# 6502-debugProbe.net
KiCad netlist of a schematic drawn in EasyEDA
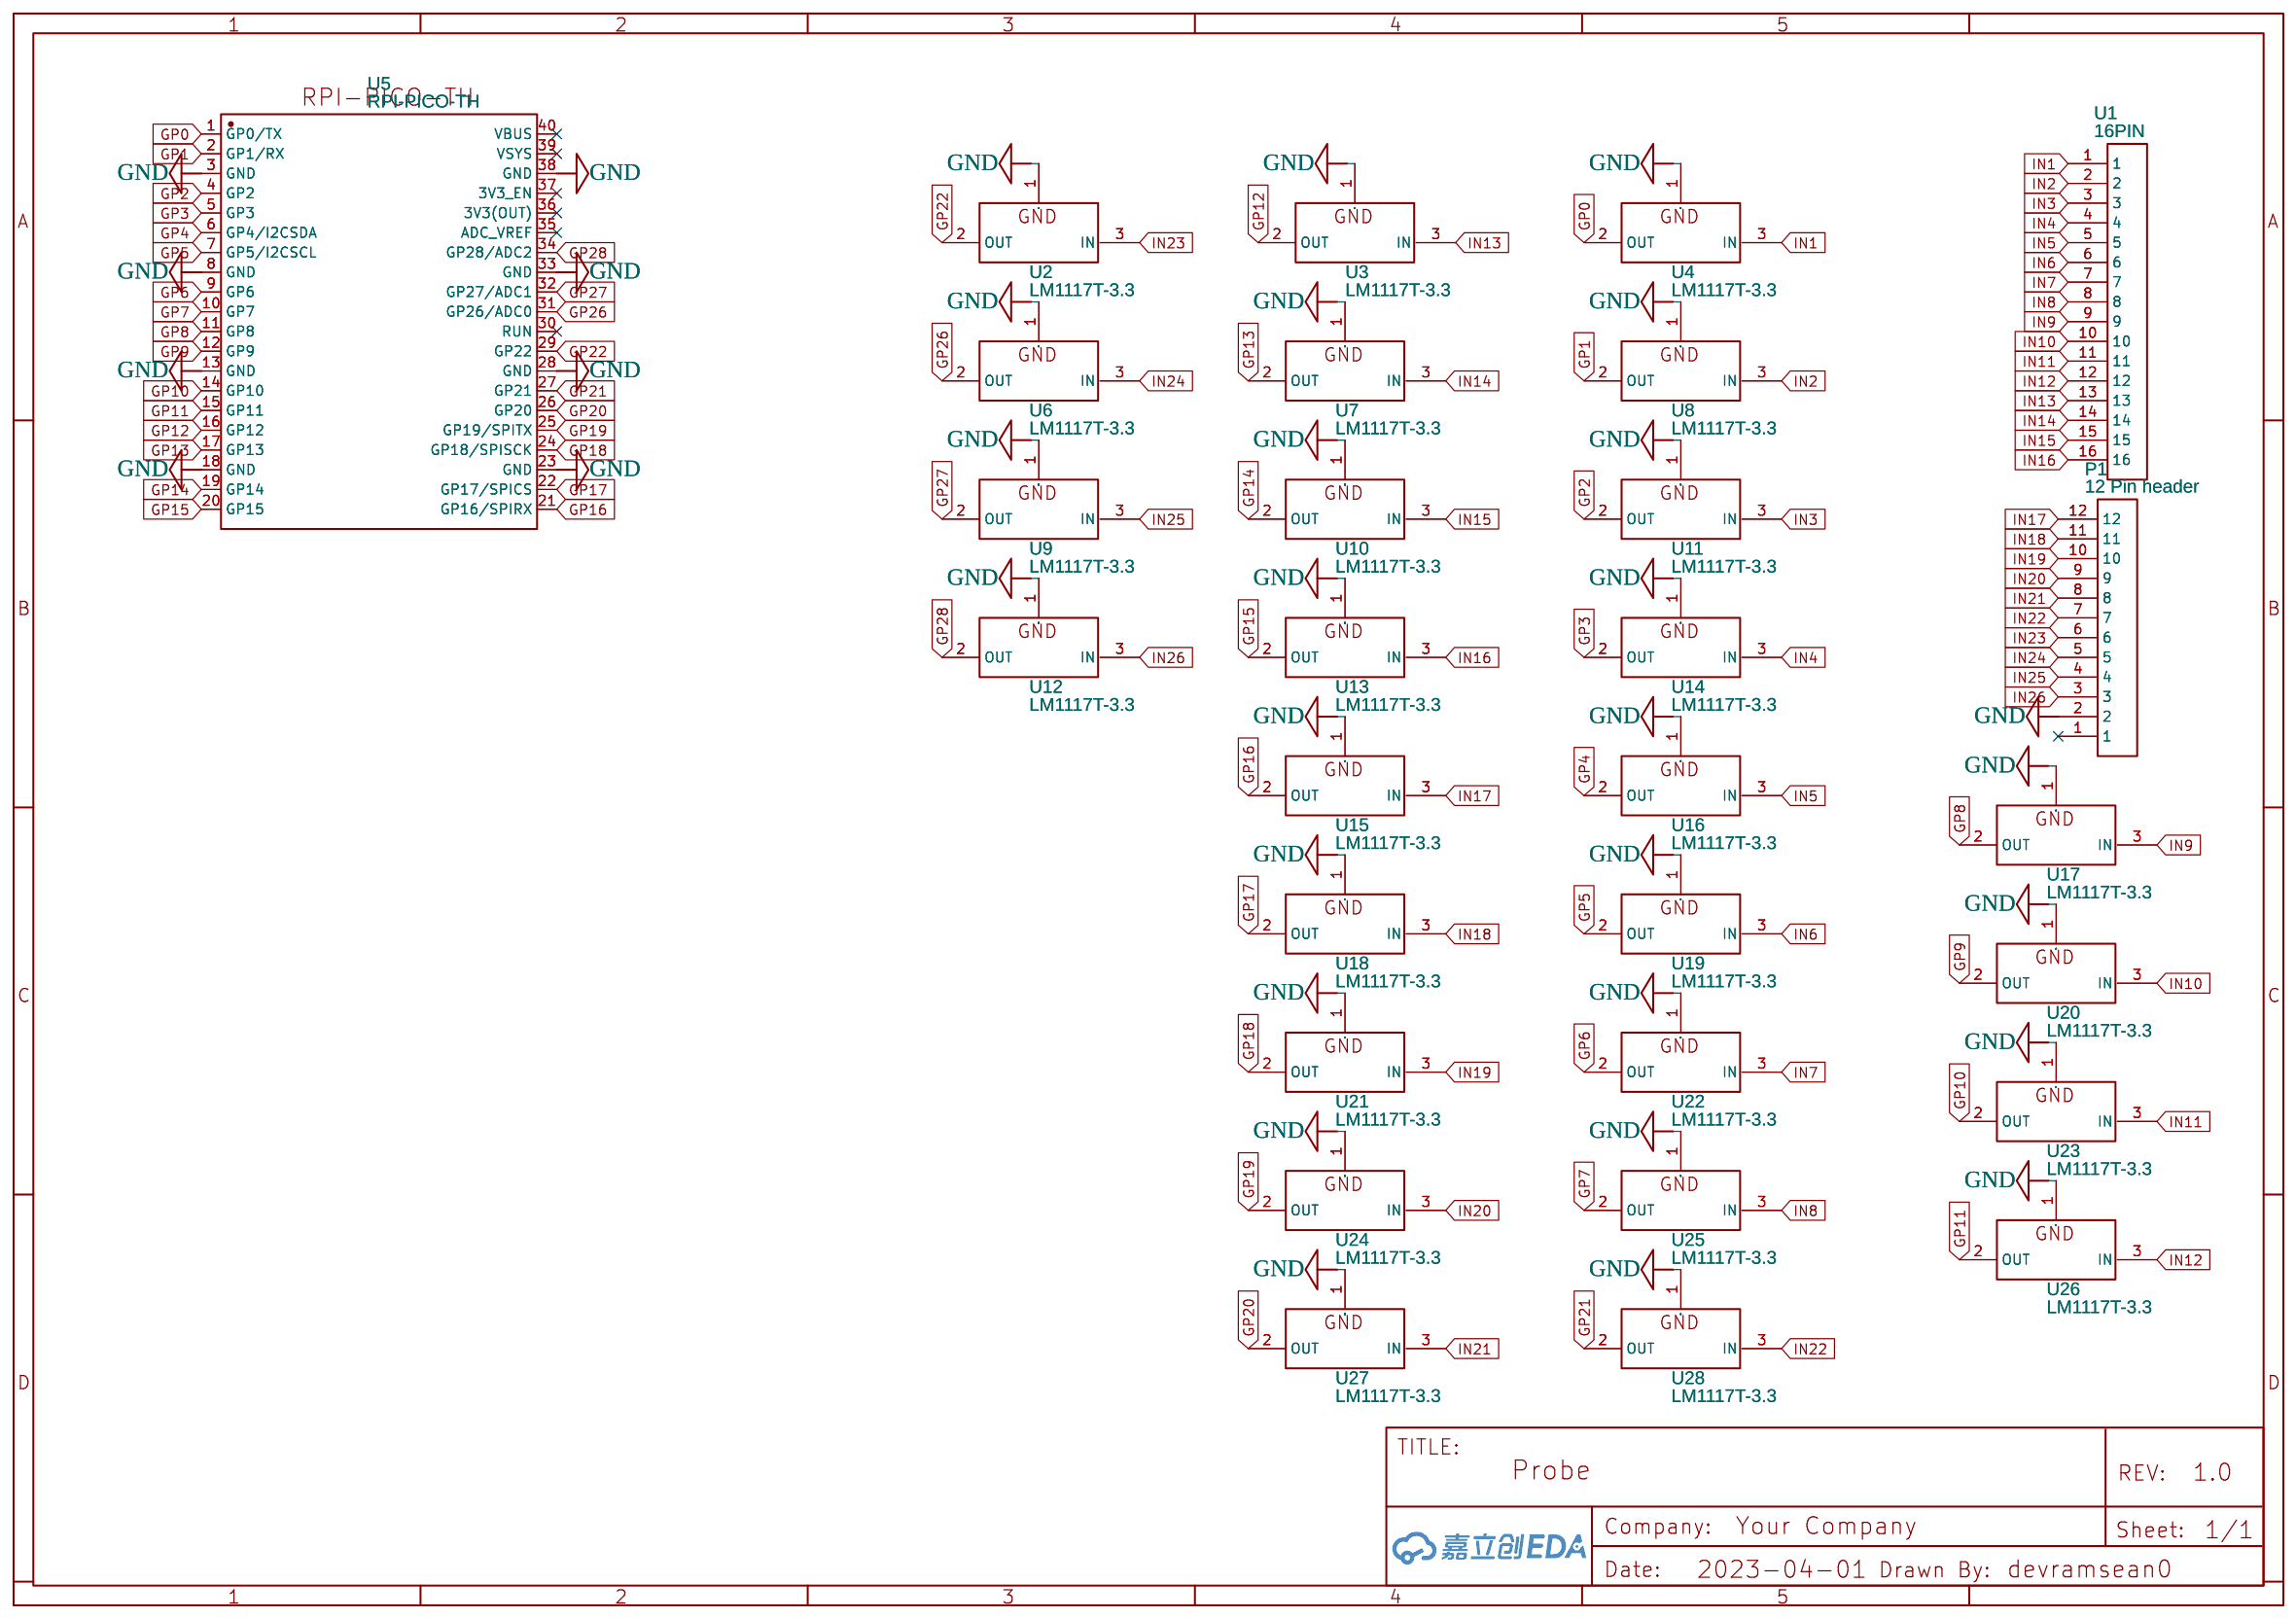
[diagram p0: schematic sheet]

(export (version "E")
  (design (tool "Eeschema 10.0.6"))
  (components
    (comp (ref "P1") (value "12 Pin header") (libsource (lib "") (part "12 Pin header")))
    (comp (ref "U1") (value "16PIN") (libsource (lib "") (part "16PIN")))
    (comp (ref "U2")
      (value "LM1117T-3.3")
      (fields (field (name "BOM_Supplier Part") "C498321"))
      (libsource (lib "") (part "LM1117T-3.3"))
    )
    (comp (ref "U3")
      (value "LM1117T-3.3")
      (fields (field (name "BOM_Supplier Part") "C498321"))
      (libsource (lib "") (part "LM1117T-3.3"))
    )
    (comp (ref "U4")
      (value "LM1117T-3.3")
      (fields (field (name "BOM_Supplier Part") "C498321"))
      (libsource (lib "") (part "LM1117T-3.3"))
    )
    (comp (ref "U5")
      (value "RPI-PICO-TH")
      (fields (field (name "BOM_Manufacturer Part") "RP2040"))
      (libsource (lib "") (part "RPI-PICO-TH"))
    )
    (comp (ref "U6")
      (value "LM1117T-3.3")
      (fields (field (name "BOM_Supplier Part") "C498321"))
      (libsource (lib "") (part "LM1117T-3.3"))
    )
    (comp (ref "U7")
      (value "LM1117T-3.3")
      (fields (field (name "BOM_Supplier Part") "C498321"))
      (libsource (lib "") (part "LM1117T-3.3"))
    )
    (comp (ref "U8")
      (value "LM1117T-3.3")
      (fields (field (name "BOM_Supplier Part") "C498321"))
      (libsource (lib "") (part "LM1117T-3.3"))
    )
    (comp (ref "U9")
      (value "LM1117T-3.3")
      (fields (field (name "BOM_Supplier Part") "C498321"))
      (libsource (lib "") (part "LM1117T-3.3"))
    )
    (comp (ref "U10")
      (value "LM1117T-3.3")
      (fields (field (name "BOM_Supplier Part") "C498321"))
      (libsource (lib "") (part "LM1117T-3.3"))
    )
    (comp (ref "U11")
      (value "LM1117T-3.3")
      (fields (field (name "BOM_Supplier Part") "C498321"))
      (libsource (lib "") (part "LM1117T-3.3"))
    )
    (comp (ref "U12")
      (value "LM1117T-3.3")
      (fields (field (name "BOM_Supplier Part") "C498321"))
      (libsource (lib "") (part "LM1117T-3.3"))
    )
    (comp (ref "U13")
      (value "LM1117T-3.3")
      (fields (field (name "BOM_Supplier Part") "C498321"))
      (libsource (lib "") (part "LM1117T-3.3"))
    )
    (comp (ref "U14")
      (value "LM1117T-3.3")
      (fields (field (name "BOM_Supplier Part") "C498321"))
      (libsource (lib "") (part "LM1117T-3.3"))
    )
    (comp (ref "U15")
      (value "LM1117T-3.3")
      (fields (field (name "BOM_Supplier Part") "C498321"))
      (libsource (lib "") (part "LM1117T-3.3"))
    )
    (comp (ref "U16")
      (value "LM1117T-3.3")
      (fields (field (name "BOM_Supplier Part") "C498321"))
      (libsource (lib "") (part "LM1117T-3.3"))
    )
    (comp (ref "U17")
      (value "LM1117T-3.3")
      (fields (field (name "BOM_Supplier Part") "C498321"))
      (libsource (lib "") (part "LM1117T-3.3"))
    )
    (comp (ref "U18")
      (value "LM1117T-3.3")
      (fields (field (name "BOM_Supplier Part") "C498321"))
      (libsource (lib "") (part "LM1117T-3.3"))
    )
    (comp (ref "U19")
      (value "LM1117T-3.3")
      (fields (field (name "BOM_Supplier Part") "C498321"))
      (libsource (lib "") (part "LM1117T-3.3"))
    )
    (comp (ref "U20")
      (value "LM1117T-3.3")
      (fields (field (name "BOM_Supplier Part") "C498321"))
      (libsource (lib "") (part "LM1117T-3.3"))
    )
    (comp (ref "U21")
      (value "LM1117T-3.3")
      (fields (field (name "BOM_Supplier Part") "C498321"))
      (libsource (lib "") (part "LM1117T-3.3"))
    )
    (comp (ref "U22")
      (value "LM1117T-3.3")
      (fields (field (name "BOM_Supplier Part") "C498321"))
      (libsource (lib "") (part "LM1117T-3.3"))
    )
    (comp (ref "U23")
      (value "LM1117T-3.3")
      (fields (field (name "BOM_Supplier Part") "C498321"))
      (libsource (lib "") (part "LM1117T-3.3"))
    )
    (comp (ref "U24")
      (value "LM1117T-3.3")
      (fields (field (name "BOM_Supplier Part") "C498321"))
      (libsource (lib "") (part "LM1117T-3.3"))
    )
    (comp (ref "U25")
      (value "LM1117T-3.3")
      (fields (field (name "BOM_Supplier Part") "C498321"))
      (libsource (lib "") (part "LM1117T-3.3"))
    )
    (comp (ref "U26")
      (value "LM1117T-3.3")
      (fields (field (name "BOM_Supplier Part") "C498321"))
      (libsource (lib "") (part "LM1117T-3.3"))
    )
    (comp (ref "U27")
      (value "LM1117T-3.3")
      (fields (field (name "BOM_Supplier Part") "C498321"))
      (libsource (lib "") (part "LM1117T-3.3"))
    )
    (comp (ref "U28")
      (value "LM1117T-3.3")
      (fields (field (name "BOM_Supplier Part") "C498321"))
      (libsource (lib "") (part "LM1117T-3.3"))
    )
  )
  (nets
    (net (code "1") (name "GND") (class "Default")
      (node (ref "P1") (pin "2") (pinfunction "2_2") (pintype "unspecified"))
      (node (ref "U10") (pin "1") (pinfunction "GND_1") (pintype "unspecified"))
      (node (ref "U11") (pin "1") (pinfunction "GND_1") (pintype "unspecified"))
      (node (ref "U12") (pin "1") (pinfunction "GND_1") (pintype "unspecified"))
      (node (ref "U13") (pin "1") (pinfunction "GND_1") (pintype "unspecified"))
      (node (ref "U14") (pin "1") (pinfunction "GND_1") (pintype "unspecified"))
      (node (ref "U15") (pin "1") (pinfunction "GND_1") (pintype "unspecified"))
      (node (ref "U16") (pin "1") (pinfunction "GND_1") (pintype "unspecified"))
      (node (ref "U17") (pin "1") (pinfunction "GND_1") (pintype "unspecified"))
      (node (ref "U18") (pin "1") (pinfunction "GND_1") (pintype "unspecified"))
      (node (ref "U19") (pin "1") (pinfunction "GND_1") (pintype "unspecified"))
      (node (ref "U2") (pin "1") (pinfunction "GND_1") (pintype "unspecified"))
      (node (ref "U20") (pin "1") (pinfunction "GND_1") (pintype "unspecified"))
      (node (ref "U21") (pin "1") (pinfunction "GND_1") (pintype "unspecified"))
      (node (ref "U22") (pin "1") (pinfunction "GND_1") (pintype "unspecified"))
      (node (ref "U23") (pin "1") (pinfunction "GND_1") (pintype "unspecified"))
      (node (ref "U24") (pin "1") (pinfunction "GND_1") (pintype "unspecified"))
      (node (ref "U25") (pin "1") (pinfunction "GND_1") (pintype "unspecified"))
      (node (ref "U26") (pin "1") (pinfunction "GND_1") (pintype "unspecified"))
      (node (ref "U27") (pin "1") (pinfunction "GND_1") (pintype "unspecified"))
      (node (ref "U28") (pin "1") (pinfunction "GND_1") (pintype "unspecified"))
      (node (ref "U3") (pin "1") (pinfunction "GND_1") (pintype "unspecified"))
      (node (ref "U4") (pin "1") (pinfunction "GND_1") (pintype "unspecified"))
      (node (ref "U5") (pin "13") (pinfunction "GND_13") (pintype "unspecified"))
      (node (ref "U5") (pin "18") (pinfunction "GND_18") (pintype "unspecified"))
      (node (ref "U5") (pin "23") (pinfunction "GND_23") (pintype "unspecified"))
      (node (ref "U5") (pin "28") (pinfunction "GND_28") (pintype "unspecified"))
      (node (ref "U5") (pin "3") (pinfunction "GND_3") (pintype "unspecified"))
      (node (ref "U5") (pin "33") (pinfunction "GND_33") (pintype "unspecified"))
      (node (ref "U5") (pin "38") (pinfunction "GND_38") (pintype "unspecified"))
      (node (ref "U5") (pin "8") (pinfunction "GND_8") (pintype "unspecified"))
      (node (ref "U6") (pin "1") (pinfunction "GND_1") (pintype "unspecified"))
      (node (ref "U7") (pin "1") (pinfunction "GND_1") (pintype "unspecified"))
      (node (ref "U8") (pin "1") (pinfunction "GND_1") (pintype "unspecified"))
      (node (ref "U9") (pin "1") (pinfunction "GND_1") (pintype "unspecified"))
    )
    (net (code "2") (name "GP0") (class "Default")
      (node (ref "U4") (pin "2") (pinfunction "OUT_2") (pintype "unspecified"))
      (node (ref "U5") (pin "1") (pinfunction "GP0/TX_1") (pintype "unspecified"))
    )
    (net (code "3") (name "GP1") (class "Default")
      (node (ref "U5") (pin "2") (pinfunction "GP1/RX_2") (pintype "unspecified"))
      (node (ref "U8") (pin "2") (pinfunction "OUT_2") (pintype "unspecified"))
    )
    (net (code "4") (name "GP2") (class "Default")
      (node (ref "U11") (pin "2") (pinfunction "OUT_2") (pintype "unspecified"))
      (node (ref "U5") (pin "4") (pinfunction "GP2_4") (pintype "unspecified"))
    )
    (net (code "5") (name "GP3") (class "Default")
      (node (ref "U14") (pin "2") (pinfunction "OUT_2") (pintype "unspecified"))
      (node (ref "U5") (pin "5") (pinfunction "GP3_5") (pintype "unspecified"))
    )
    (net (code "6") (name "GP4") (class "Default")
      (node (ref "U16") (pin "2") (pinfunction "OUT_2") (pintype "unspecified"))
      (node (ref "U5") (pin "6") (pinfunction "GP4/I2CSDA_6") (pintype "unspecified"))
    )
    (net (code "7") (name "GP5") (class "Default")
      (node (ref "U19") (pin "2") (pinfunction "OUT_2") (pintype "unspecified"))
      (node (ref "U5") (pin "7") (pinfunction "GP5/I2CSCL_7") (pintype "unspecified"))
    )
    (net (code "8") (name "GP6") (class "Default")
      (node (ref "U22") (pin "2") (pinfunction "OUT_2") (pintype "unspecified"))
      (node (ref "U5") (pin "9") (pinfunction "GP6_9") (pintype "unspecified"))
    )
    (net (code "9") (name "GP7") (class "Default")
      (node (ref "U25") (pin "2") (pinfunction "OUT_2") (pintype "unspecified"))
      (node (ref "U5") (pin "10") (pinfunction "GP7_10") (pintype "unspecified"))
    )
    (net (code "10") (name "GP8") (class "Default")
      (node (ref "U17") (pin "2") (pinfunction "OUT_2") (pintype "unspecified"))
      (node (ref "U5") (pin "11") (pinfunction "GP8_11") (pintype "unspecified"))
    )
    (net (code "11") (name "GP9") (class "Default")
      (node (ref "U20") (pin "2") (pinfunction "OUT_2") (pintype "unspecified"))
      (node (ref "U5") (pin "12") (pinfunction "GP9_12") (pintype "unspecified"))
    )
    (net (code "12") (name "GP10") (class "Default")
      (node (ref "U23") (pin "2") (pinfunction "OUT_2") (pintype "unspecified"))
      (node (ref "U5") (pin "14") (pinfunction "GP10_14") (pintype "unspecified"))
    )
    (net (code "13") (name "GP11") (class "Default")
      (node (ref "U26") (pin "2") (pinfunction "OUT_2") (pintype "unspecified"))
      (node (ref "U5") (pin "15") (pinfunction "GP11_15") (pintype "unspecified"))
    )
    (net (code "14") (name "GP12") (class "Default")
      (node (ref "U3") (pin "2") (pinfunction "OUT_2") (pintype "unspecified"))
      (node (ref "U5") (pin "16") (pinfunction "GP12_16") (pintype "unspecified"))
    )
    (net (code "15") (name "GP13") (class "Default")
      (node (ref "U5") (pin "17") (pinfunction "GP13_17") (pintype "unspecified"))
      (node (ref "U7") (pin "2") (pinfunction "OUT_2") (pintype "unspecified"))
    )
    (net (code "16") (name "GP14") (class "Default")
      (node (ref "U10") (pin "2") (pinfunction "OUT_2") (pintype "unspecified"))
      (node (ref "U5") (pin "19") (pinfunction "GP14_19") (pintype "unspecified"))
    )
    (net (code "17") (name "GP15") (class "Default")
      (node (ref "U13") (pin "2") (pinfunction "OUT_2") (pintype "unspecified"))
      (node (ref "U5") (pin "20") (pinfunction "GP15_20") (pintype "unspecified"))
    )
    (net (code "18") (name "GP16") (class "Default")
      (node (ref "U15") (pin "2") (pinfunction "OUT_2") (pintype "unspecified"))
      (node (ref "U5") (pin "21") (pinfunction "GP16/SPIRX_21") (pintype "unspecified"))
    )
    (net (code "19") (name "GP17") (class "Default")
      (node (ref "U18") (pin "2") (pinfunction "OUT_2") (pintype "unspecified"))
      (node (ref "U5") (pin "22") (pinfunction "GP17/SPICS_22") (pintype "unspecified"))
    )
    (net (code "20") (name "GP18") (class "Default")
      (node (ref "U21") (pin "2") (pinfunction "OUT_2") (pintype "unspecified"))
      (node (ref "U5") (pin "24") (pinfunction "GP18/SPISCK_24") (pintype "unspecified"))
    )
    (net (code "21") (name "GP19") (class "Default")
      (node (ref "U24") (pin "2") (pinfunction "OUT_2") (pintype "unspecified"))
      (node (ref "U5") (pin "25") (pinfunction "GP19/SPITX_25") (pintype "unspecified"))
    )
    (net (code "22") (name "GP20") (class "Default")
      (node (ref "U27") (pin "2") (pinfunction "OUT_2") (pintype "unspecified"))
      (node (ref "U5") (pin "26") (pinfunction "GP20_26") (pintype "unspecified"))
    )
    (net (code "23") (name "GP21") (class "Default")
      (node (ref "U28") (pin "2") (pinfunction "OUT_2") (pintype "unspecified"))
      (node (ref "U5") (pin "27") (pinfunction "GP21_27") (pintype "unspecified"))
    )
    (net (code "24") (name "GP22") (class "Default")
      (node (ref "U2") (pin "2") (pinfunction "OUT_2") (pintype "unspecified"))
      (node (ref "U5") (pin "29") (pinfunction "GP22_29") (pintype "unspecified"))
    )
    (net (code "25") (name "GP26") (class "Default")
      (node (ref "U5") (pin "31") (pinfunction "GP26/ADC0_31") (pintype "unspecified"))
      (node (ref "U6") (pin "2") (pinfunction "OUT_2") (pintype "unspecified"))
    )
    (net (code "26") (name "GP27") (class "Default")
      (node (ref "U5") (pin "32") (pinfunction "GP27/ADC1_32") (pintype "unspecified"))
      (node (ref "U9") (pin "2") (pinfunction "OUT_2") (pintype "unspecified"))
    )
    (net (code "27") (name "GP28") (class "Default")
      (node (ref "U12") (pin "2") (pinfunction "OUT_2") (pintype "unspecified"))
      (node (ref "U5") (pin "34") (pinfunction "GP28/ADC2_34") (pintype "unspecified"))
    )
    (net (code "28") (name "IN1") (class "Default")
      (node (ref "U1") (pin "1") (pinfunction "1_1") (pintype "unspecified"))
      (node (ref "U4") (pin "3") (pinfunction "IN_3") (pintype "unspecified"))
    )
    (net (code "29") (name "IN2") (class "Default")
      (node (ref "U1") (pin "2") (pinfunction "2_2") (pintype "unspecified"))
      (node (ref "U8") (pin "3") (pinfunction "IN_3") (pintype "unspecified"))
    )
    (net (code "30") (name "IN3") (class "Default")
      (node (ref "U1") (pin "3") (pinfunction "3_3") (pintype "unspecified"))
      (node (ref "U11") (pin "3") (pinfunction "IN_3") (pintype "unspecified"))
    )
    (net (code "31") (name "IN4") (class "Default")
      (node (ref "U1") (pin "4") (pinfunction "4_4") (pintype "unspecified"))
      (node (ref "U14") (pin "3") (pinfunction "IN_3") (pintype "unspecified"))
    )
    (net (code "32") (name "IN5") (class "Default")
      (node (ref "U1") (pin "5") (pinfunction "5_5") (pintype "unspecified"))
      (node (ref "U16") (pin "3") (pinfunction "IN_3") (pintype "unspecified"))
    )
    (net (code "33") (name "IN6") (class "Default")
      (node (ref "U1") (pin "6") (pinfunction "6_6") (pintype "unspecified"))
      (node (ref "U19") (pin "3") (pinfunction "IN_3") (pintype "unspecified"))
    )
    (net (code "34") (name "IN7") (class "Default")
      (node (ref "U1") (pin "7") (pinfunction "7_7") (pintype "unspecified"))
      (node (ref "U22") (pin "3") (pinfunction "IN_3") (pintype "unspecified"))
    )
    (net (code "35") (name "IN8") (class "Default")
      (node (ref "U1") (pin "8") (pinfunction "8_8") (pintype "unspecified"))
      (node (ref "U25") (pin "3") (pinfunction "IN_3") (pintype "unspecified"))
    )
    (net (code "36") (name "IN9") (class "Default")
      (node (ref "U1") (pin "9") (pinfunction "9_9") (pintype "unspecified"))
      (node (ref "U17") (pin "3") (pinfunction "IN_3") (pintype "unspecified"))
    )
    (net (code "37") (name "IN10") (class "Default")
      (node (ref "U1") (pin "10") (pinfunction "10_10") (pintype "unspecified"))
      (node (ref "U20") (pin "3") (pinfunction "IN_3") (pintype "unspecified"))
    )
    (net (code "38") (name "IN11") (class "Default")
      (node (ref "U1") (pin "11") (pinfunction "11_11") (pintype "unspecified"))
      (node (ref "U23") (pin "3") (pinfunction "IN_3") (pintype "unspecified"))
    )
    (net (code "39") (name "IN12") (class "Default")
      (node (ref "U1") (pin "12") (pinfunction "12_12") (pintype "unspecified"))
      (node (ref "U26") (pin "3") (pinfunction "IN_3") (pintype "unspecified"))
    )
    (net (code "40") (name "IN13") (class "Default")
      (node (ref "U1") (pin "13") (pinfunction "13_13") (pintype "unspecified"))
      (node (ref "U3") (pin "3") (pinfunction "IN_3") (pintype "unspecified"))
    )
    (net (code "41") (name "IN14") (class "Default")
      (node (ref "U1") (pin "14") (pinfunction "14_14") (pintype "unspecified"))
      (node (ref "U7") (pin "3") (pinfunction "IN_3") (pintype "unspecified"))
    )
    (net (code "42") (name "IN15") (class "Default")
      (node (ref "U1") (pin "15") (pinfunction "15_15") (pintype "unspecified"))
      (node (ref "U10") (pin "3") (pinfunction "IN_3") (pintype "unspecified"))
    )
    (net (code "43") (name "IN16") (class "Default")
      (node (ref "U1") (pin "16") (pinfunction "16_16") (pintype "unspecified"))
      (node (ref "U13") (pin "3") (pinfunction "IN_3") (pintype "unspecified"))
    )
    (net (code "44") (name "IN17") (class "Default")
      (node (ref "P1") (pin "12") (pinfunction "12_12") (pintype "unspecified"))
      (node (ref "U15") (pin "3") (pinfunction "IN_3") (pintype "unspecified"))
    )
    (net (code "45") (name "IN18") (class "Default")
      (node (ref "P1") (pin "11") (pinfunction "11_11") (pintype "unspecified"))
      (node (ref "U18") (pin "3") (pinfunction "IN_3") (pintype "unspecified"))
    )
    (net (code "46") (name "IN19") (class "Default")
      (node (ref "P1") (pin "10") (pinfunction "10_10") (pintype "unspecified"))
      (node (ref "U21") (pin "3") (pinfunction "IN_3") (pintype "unspecified"))
    )
    (net (code "47") (name "IN20") (class "Default")
      (node (ref "P1") (pin "9") (pinfunction "9_9") (pintype "unspecified"))
      (node (ref "U24") (pin "3") (pinfunction "IN_3") (pintype "unspecified"))
    )
    (net (code "48") (name "IN21") (class "Default")
      (node (ref "P1") (pin "8") (pinfunction "8_8") (pintype "unspecified"))
      (node (ref "U27") (pin "3") (pinfunction "IN_3") (pintype "unspecified"))
    )
    (net (code "49") (name "IN22") (class "Default")
      (node (ref "P1") (pin "7") (pinfunction "7_7") (pintype "unspecified"))
      (node (ref "U28") (pin "3") (pinfunction "IN_3") (pintype "unspecified"))
    )
    (net (code "50") (name "IN23") (class "Default")
      (node (ref "P1") (pin "6") (pinfunction "6_6") (pintype "unspecified"))
      (node (ref "U2") (pin "3") (pinfunction "IN_3") (pintype "unspecified"))
    )
    (net (code "51") (name "IN24") (class "Default")
      (node (ref "P1") (pin "5") (pinfunction "5_5") (pintype "unspecified"))
      (node (ref "U6") (pin "3") (pinfunction "IN_3") (pintype "unspecified"))
    )
    (net (code "52") (name "IN25") (class "Default")
      (node (ref "P1") (pin "4") (pinfunction "4_4") (pintype "unspecified"))
      (node (ref "U9") (pin "3") (pinfunction "IN_3") (pintype "unspecified"))
    )
    (net (code "53") (name "IN26") (class "Default")
      (node (ref "P1") (pin "3") (pinfunction "3_3") (pintype "unspecified"))
      (node (ref "U12") (pin "3") (pinfunction "IN_3") (pintype "unspecified"))
    )
    (net (code "54") (name "unconnected-(P1-Pad1)") (class "Default")
      (node (ref "P1") (pin "1") (pinfunction "1_1") (pintype "unspecified+no_connect"))
    )
    (net (code "55") (name "unconnected-(U5-3V3(OUT)-Pad36)") (class "Default")
      (node (ref "U5") (pin "36") (pinfunction "3V3(OUT)_36") (pintype "unspecified+no_connect"))
    )
    (net (code "56") (name "unconnected-(U5-3V3_EN-Pad37)") (class "Default")
      (node (ref "U5") (pin "37") (pinfunction "3V3_EN_37") (pintype "unspecified+no_connect"))
    )
    (net (code "57") (name "unconnected-(U5-ADC_VREF-Pad35)") (class "Default")
      (node (ref "U5") (pin "35") (pinfunction "ADC_VREF_35") (pintype "unspecified+no_connect"))
    )
    (net (code "58") (name "unconnected-(U5-RUN-Pad30)") (class "Default")
      (node (ref "U5") (pin "30") (pinfunction "RUN_30") (pintype "unspecified+no_connect"))
    )
    (net (code "59") (name "unconnected-(U5-VBUS-Pad40)") (class "Default")
      (node (ref "U5") (pin "40") (pinfunction "VBUS_40") (pintype "unspecified+no_connect"))
    )
    (net (code "60") (name "unconnected-(U5-VSYS-Pad39)") (class "Default")
      (node (ref "U5") (pin "39") (pinfunction "VSYS_39") (pintype "unspecified+no_connect"))
    )
  )
)
